# cmdc0de-apa104.net
KiCad netlist of a schematic drawn in EAGLE
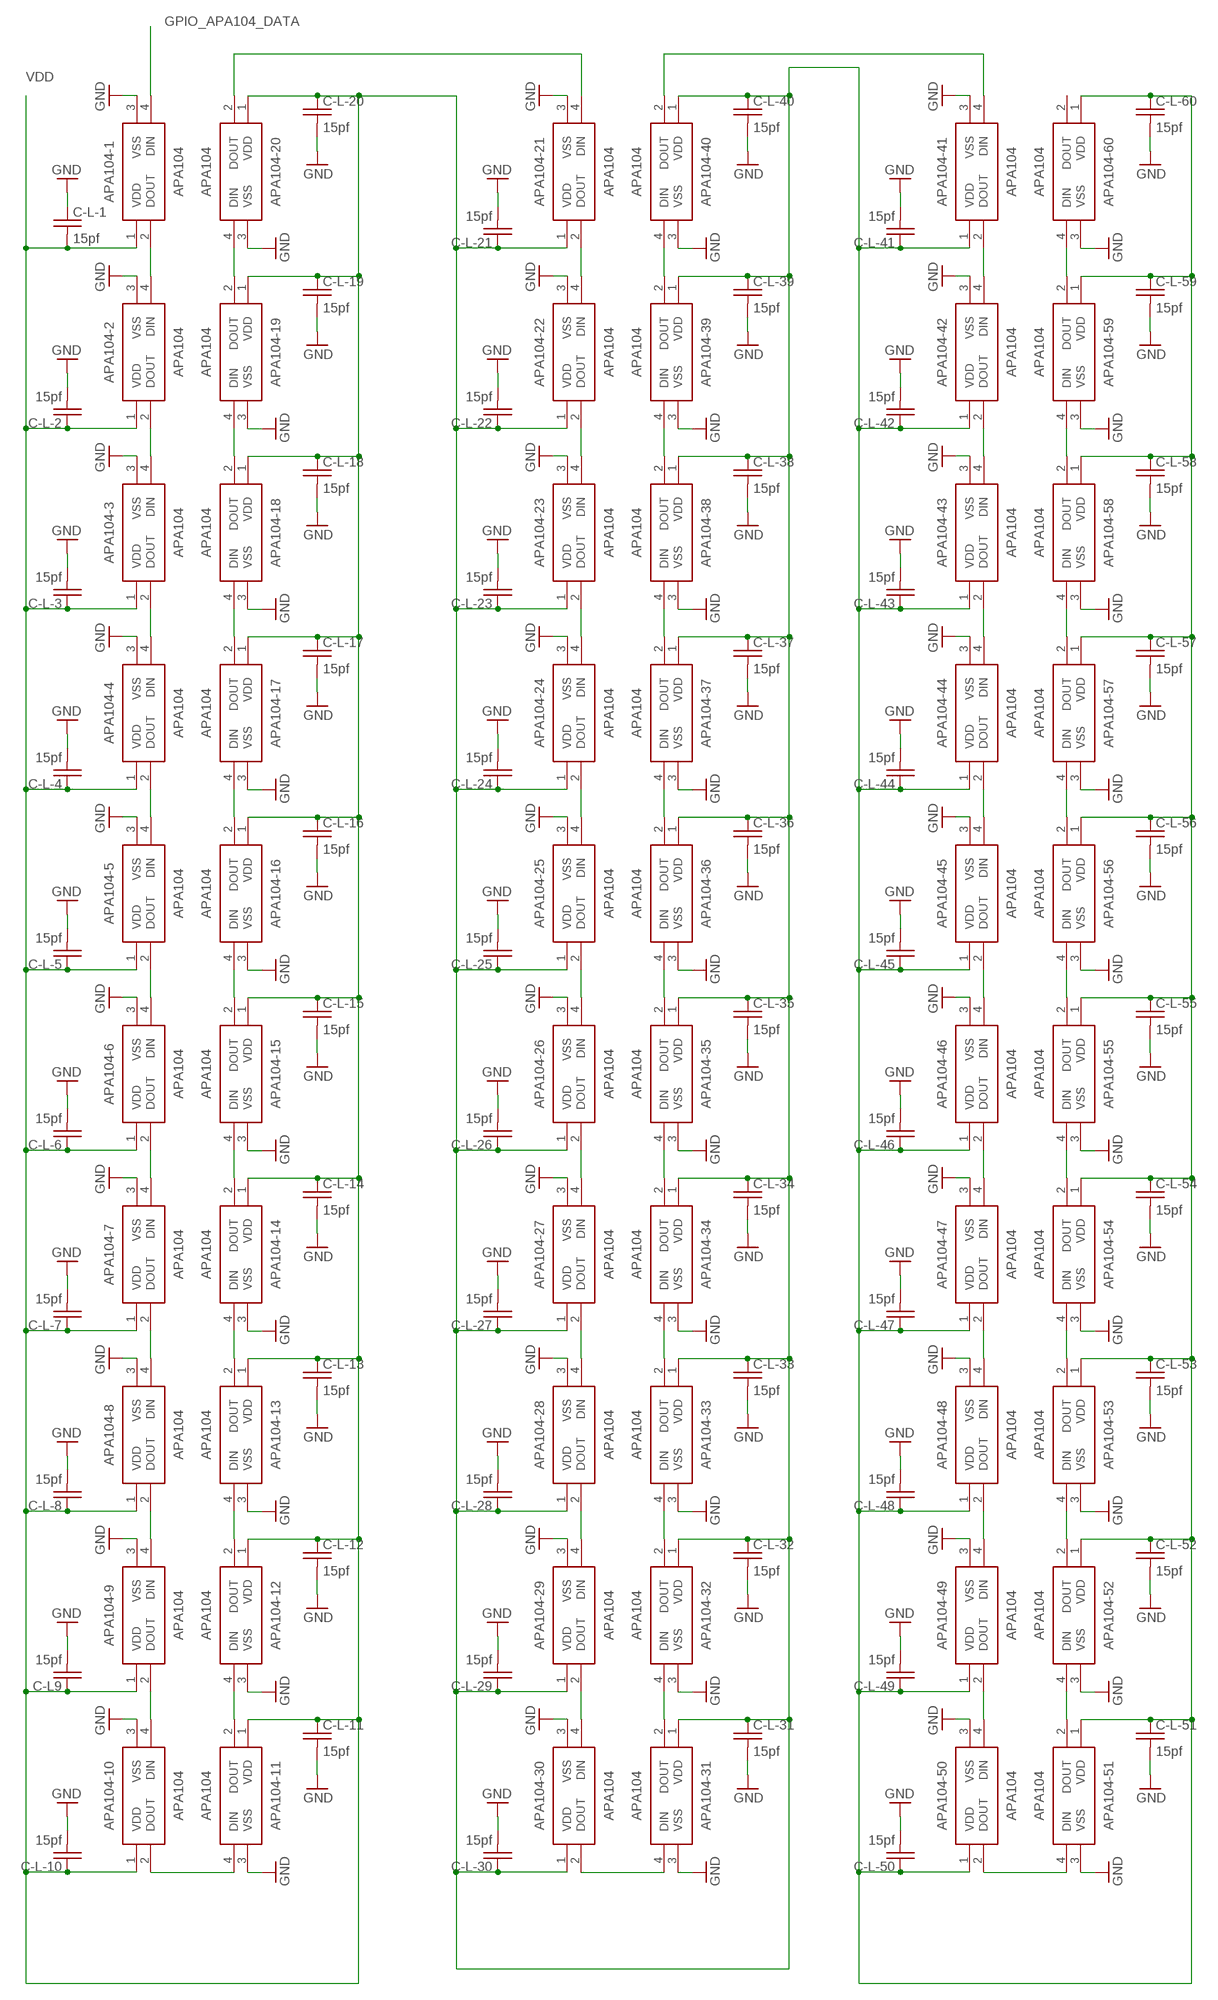
[diagram p0: schematic, sheet 1]
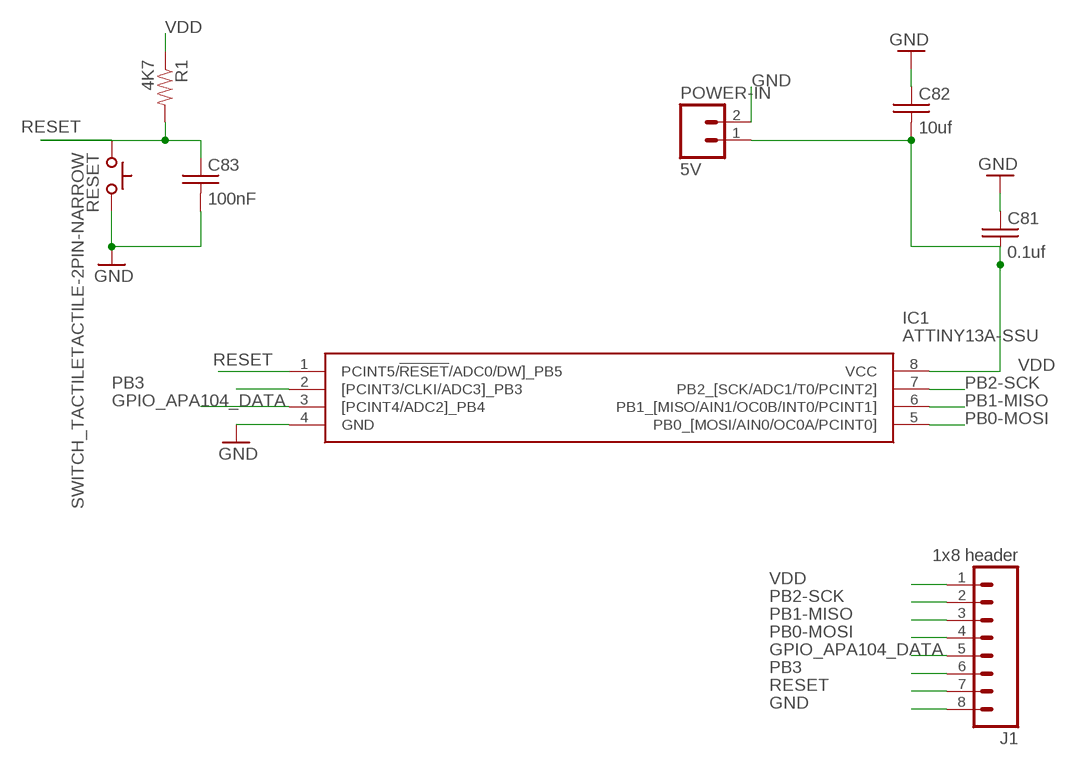
[diagram p1: schematic, sheet 2]

(export (version "E")
  (design (tool "Eeschema 10.0.6"))
  (components
    (comp (ref "C81")
      (value "0.1uf")
      (footprint "eagle-import:C0805-VOLTA")
      (libsource (lib "eagle-import") (part "C-USC0805-VOLTERA"))
    )
    (comp (ref "C82")
      (value "10uf")
      (footprint "eagle-import:C0805-VOLTA")
      (libsource (lib "eagle-import") (part "C-USC0805-VOLTERA"))
    )
    (comp (ref "C83")
      (value "100nF")
      (footprint "eagle-import:C0805-VOLTA")
      (libsource (lib "eagle-import") (part "C-USC0805-VOLTERA"))
    )
    (comp (ref "IC1")
      (value "ATTINY13A-SSU")
      (footprint "eagle-import:SOIC127P600X175-8N")
      (fields (field (name "RS_PART_NUMBER") "9214573"))
      (libsource (lib "eagle-import") (part "ATTINY13A-SSU"))
    )
    (comp (ref "J1")
      (value "1x8 header")
      (footprint "eagle-import:1X08")
      (libsource (lib "eagle-import") (part "M08SILK_FEMALE_PTH"))
    )
    (comp (ref "POWER-IN")
      (value "5V")
      (footprint "eagle-import:1X02")
      (libsource (lib "eagle-import") (part "M02PTH"))
    )
    (comp (ref "R1")
      (value "4K7")
      (footprint "eagle-import:0805")
      (libsource (lib "eagle-import") (part "RESISTOR0805-RES"))
    )
    (comp (ref "RESET")
      (value "SWITCH_TACTILETACTILE-2PIN-NARROW")
      (footprint "eagle-import:TACTILE-2PIN-NARROW")
      (libsource (lib "eagle-import") (part "SWITCH_TACTILETACTILE-2PIN-NARROW"))
    )
    (comp (ref "APA104-1")
      (value "APA104")
      (footprint "eagle-import:APA104")
      (libsource (lib "eagle-import") (part "APA104"))
    )
    (comp (ref "APA104-2")
      (value "APA104")
      (footprint "eagle-import:APA104")
      (libsource (lib "eagle-import") (part "APA104"))
    )
    (comp (ref "APA104-3")
      (value "APA104")
      (footprint "eagle-import:APA104")
      (libsource (lib "eagle-import") (part "APA104"))
    )
    (comp (ref "APA104-4")
      (value "APA104")
      (footprint "eagle-import:APA104")
      (libsource (lib "eagle-import") (part "APA104"))
    )
    (comp (ref "APA104-5")
      (value "APA104")
      (footprint "eagle-import:APA104")
      (libsource (lib "eagle-import") (part "APA104"))
    )
    (comp (ref "APA104-6")
      (value "APA104")
      (footprint "eagle-import:APA104")
      (libsource (lib "eagle-import") (part "APA104"))
    )
    (comp (ref "APA104-7")
      (value "APA104")
      (footprint "eagle-import:APA104")
      (libsource (lib "eagle-import") (part "APA104"))
    )
    (comp (ref "APA104-8")
      (value "APA104")
      (footprint "eagle-import:APA104")
      (libsource (lib "eagle-import") (part "APA104"))
    )
    (comp (ref "APA104-9")
      (value "APA104")
      (footprint "eagle-import:APA104")
      (libsource (lib "eagle-import") (part "APA104"))
    )
    (comp (ref "APA104-10")
      (value "APA104")
      (footprint "eagle-import:APA104")
      (libsource (lib "eagle-import") (part "APA104"))
    )
    (comp (ref "APA104-11")
      (value "APA104")
      (footprint "eagle-import:APA104")
      (libsource (lib "eagle-import") (part "APA104"))
    )
    (comp (ref "APA104-12")
      (value "APA104")
      (footprint "eagle-import:APA104")
      (libsource (lib "eagle-import") (part "APA104"))
    )
    (comp (ref "APA104-13")
      (value "APA104")
      (footprint "eagle-import:APA104")
      (libsource (lib "eagle-import") (part "APA104"))
    )
    (comp (ref "APA104-14")
      (value "APA104")
      (footprint "eagle-import:APA104")
      (libsource (lib "eagle-import") (part "APA104"))
    )
    (comp (ref "APA104-15")
      (value "APA104")
      (footprint "eagle-import:APA104")
      (libsource (lib "eagle-import") (part "APA104"))
    )
    (comp (ref "APA104-16")
      (value "APA104")
      (footprint "eagle-import:APA104")
      (libsource (lib "eagle-import") (part "APA104"))
    )
    (comp (ref "APA104-17")
      (value "APA104")
      (footprint "eagle-import:APA104")
      (libsource (lib "eagle-import") (part "APA104"))
    )
    (comp (ref "APA104-18")
      (value "APA104")
      (footprint "eagle-import:APA104")
      (libsource (lib "eagle-import") (part "APA104"))
    )
    (comp (ref "APA104-19")
      (value "APA104")
      (footprint "eagle-import:APA104")
      (libsource (lib "eagle-import") (part "APA104"))
    )
    (comp (ref "APA104-20")
      (value "APA104")
      (footprint "eagle-import:APA104")
      (libsource (lib "eagle-import") (part "APA104"))
    )
    (comp (ref "APA104-21")
      (value "APA104")
      (footprint "eagle-import:APA104")
      (libsource (lib "eagle-import") (part "APA104"))
    )
    (comp (ref "APA104-22")
      (value "APA104")
      (footprint "eagle-import:APA104")
      (libsource (lib "eagle-import") (part "APA104"))
    )
    (comp (ref "APA104-23")
      (value "APA104")
      (footprint "eagle-import:APA104")
      (libsource (lib "eagle-import") (part "APA104"))
    )
    (comp (ref "APA104-24")
      (value "APA104")
      (footprint "eagle-import:APA104")
      (libsource (lib "eagle-import") (part "APA104"))
    )
    (comp (ref "APA104-25")
      (value "APA104")
      (footprint "eagle-import:APA104")
      (libsource (lib "eagle-import") (part "APA104"))
    )
    (comp (ref "APA104-26")
      (value "APA104")
      (footprint "eagle-import:APA104")
      (libsource (lib "eagle-import") (part "APA104"))
    )
    (comp (ref "APA104-27")
      (value "APA104")
      (footprint "eagle-import:APA104")
      (libsource (lib "eagle-import") (part "APA104"))
    )
    (comp (ref "APA104-28")
      (value "APA104")
      (footprint "eagle-import:APA104")
      (libsource (lib "eagle-import") (part "APA104"))
    )
    (comp (ref "APA104-29")
      (value "APA104")
      (footprint "eagle-import:APA104")
      (libsource (lib "eagle-import") (part "APA104"))
    )
    (comp (ref "APA104-30")
      (value "APA104")
      (footprint "eagle-import:APA104")
      (libsource (lib "eagle-import") (part "APA104"))
    )
    (comp (ref "APA104-31")
      (value "APA104")
      (footprint "eagle-import:APA104")
      (libsource (lib "eagle-import") (part "APA104"))
    )
    (comp (ref "APA104-32")
      (value "APA104")
      (footprint "eagle-import:APA104")
      (libsource (lib "eagle-import") (part "APA104"))
    )
    (comp (ref "APA104-33")
      (value "APA104")
      (footprint "eagle-import:APA104")
      (libsource (lib "eagle-import") (part "APA104"))
    )
    (comp (ref "APA104-34")
      (value "APA104")
      (footprint "eagle-import:APA104")
      (libsource (lib "eagle-import") (part "APA104"))
    )
    (comp (ref "APA104-35")
      (value "APA104")
      (footprint "eagle-import:APA104")
      (libsource (lib "eagle-import") (part "APA104"))
    )
    (comp (ref "APA104-36")
      (value "APA104")
      (footprint "eagle-import:APA104")
      (libsource (lib "eagle-import") (part "APA104"))
    )
    (comp (ref "APA104-37")
      (value "APA104")
      (footprint "eagle-import:APA104")
      (libsource (lib "eagle-import") (part "APA104"))
    )
    (comp (ref "APA104-38")
      (value "APA104")
      (footprint "eagle-import:APA104")
      (libsource (lib "eagle-import") (part "APA104"))
    )
    (comp (ref "APA104-39")
      (value "APA104")
      (footprint "eagle-import:APA104")
      (libsource (lib "eagle-import") (part "APA104"))
    )
    (comp (ref "APA104-40")
      (value "APA104")
      (footprint "eagle-import:APA104")
      (libsource (lib "eagle-import") (part "APA104"))
    )
    (comp (ref "APA104-41")
      (value "APA104")
      (footprint "eagle-import:APA104")
      (libsource (lib "eagle-import") (part "APA104"))
    )
    (comp (ref "APA104-42")
      (value "APA104")
      (footprint "eagle-import:APA104")
      (libsource (lib "eagle-import") (part "APA104"))
    )
    (comp (ref "APA104-43")
      (value "APA104")
      (footprint "eagle-import:APA104")
      (libsource (lib "eagle-import") (part "APA104"))
    )
    (comp (ref "APA104-44")
      (value "APA104")
      (footprint "eagle-import:APA104")
      (libsource (lib "eagle-import") (part "APA104"))
    )
    (comp (ref "APA104-45")
      (value "APA104")
      (footprint "eagle-import:APA104")
      (libsource (lib "eagle-import") (part "APA104"))
    )
    (comp (ref "APA104-46")
      (value "APA104")
      (footprint "eagle-import:APA104")
      (libsource (lib "eagle-import") (part "APA104"))
    )
    (comp (ref "APA104-47")
      (value "APA104")
      (footprint "eagle-import:APA104")
      (libsource (lib "eagle-import") (part "APA104"))
    )
    (comp (ref "APA104-48")
      (value "APA104")
      (footprint "eagle-import:APA104")
      (libsource (lib "eagle-import") (part "APA104"))
    )
    (comp (ref "APA104-49")
      (value "APA104")
      (footprint "eagle-import:APA104")
      (libsource (lib "eagle-import") (part "APA104"))
    )
    (comp (ref "APA104-50")
      (value "APA104")
      (footprint "eagle-import:APA104")
      (libsource (lib "eagle-import") (part "APA104"))
    )
    (comp (ref "APA104-51")
      (value "APA104")
      (footprint "eagle-import:APA104")
      (libsource (lib "eagle-import") (part "APA104"))
    )
    (comp (ref "APA104-52")
      (value "APA104")
      (footprint "eagle-import:APA104")
      (libsource (lib "eagle-import") (part "APA104"))
    )
    (comp (ref "APA104-53")
      (value "APA104")
      (footprint "eagle-import:APA104")
      (libsource (lib "eagle-import") (part "APA104"))
    )
    (comp (ref "APA104-54")
      (value "APA104")
      (footprint "eagle-import:APA104")
      (libsource (lib "eagle-import") (part "APA104"))
    )
    (comp (ref "APA104-55")
      (value "APA104")
      (footprint "eagle-import:APA104")
      (libsource (lib "eagle-import") (part "APA104"))
    )
    (comp (ref "APA104-56")
      (value "APA104")
      (footprint "eagle-import:APA104")
      (libsource (lib "eagle-import") (part "APA104"))
    )
    (comp (ref "APA104-57")
      (value "APA104")
      (footprint "eagle-import:APA104")
      (libsource (lib "eagle-import") (part "APA104"))
    )
    (comp (ref "APA104-58")
      (value "APA104")
      (footprint "eagle-import:APA104")
      (libsource (lib "eagle-import") (part "APA104"))
    )
    (comp (ref "APA104-59")
      (value "APA104")
      (footprint "eagle-import:APA104")
      (libsource (lib "eagle-import") (part "APA104"))
    )
    (comp (ref "APA104-60")
      (value "APA104")
      (footprint "eagle-import:APA104")
      (libsource (lib "eagle-import") (part "APA104"))
    )
    (comp (ref "C-L-1")
      (value "15pf")
      (footprint "eagle-import:C0805-VOLTA")
      (libsource (lib "eagle-import") (part "C-USC0805-VOLTERA"))
    )
    (comp (ref "C-L-2")
      (value "15pf")
      (footprint "eagle-import:C0805-VOLTA")
      (libsource (lib "eagle-import") (part "C-USC0805-VOLTERA"))
    )
    (comp (ref "C-L-3")
      (value "15pf")
      (footprint "eagle-import:C0805-VOLTA")
      (libsource (lib "eagle-import") (part "C-USC0805-VOLTERA"))
    )
    (comp (ref "C-L-4")
      (value "15pf")
      (footprint "eagle-import:C0805-VOLTA")
      (libsource (lib "eagle-import") (part "C-USC0805-VOLTERA"))
    )
    (comp (ref "C-L-5")
      (value "15pf")
      (footprint "eagle-import:C0805-VOLTA")
      (libsource (lib "eagle-import") (part "C-USC0805-VOLTERA"))
    )
    (comp (ref "C-L-6")
      (value "15pf")
      (footprint "eagle-import:C0805-VOLTA")
      (libsource (lib "eagle-import") (part "C-USC0805-VOLTERA"))
    )
    (comp (ref "C-L-7")
      (value "15pf")
      (footprint "eagle-import:C0805-VOLTA")
      (libsource (lib "eagle-import") (part "C-USC0805-VOLTERA"))
    )
    (comp (ref "C-L-8")
      (value "15pf")
      (footprint "eagle-import:C0805-VOLTA")
      (libsource (lib "eagle-import") (part "C-USC0805-VOLTERA"))
    )
    (comp (ref "C-L-10")
      (value "15pf")
      (footprint "eagle-import:C0805-VOLTA")
      (libsource (lib "eagle-import") (part "C-USC0805-VOLTERA"))
    )
    (comp (ref "C-L-11")
      (value "15pf")
      (footprint "eagle-import:C0805-VOLTA")
      (libsource (lib "eagle-import") (part "C-USC0805-VOLTERA"))
    )
    (comp (ref "C-L-12")
      (value "15pf")
      (footprint "eagle-import:C0805-VOLTA")
      (libsource (lib "eagle-import") (part "C-USC0805-VOLTERA"))
    )
    (comp (ref "C-L-13")
      (value "15pf")
      (footprint "eagle-import:C0805-VOLTA")
      (libsource (lib "eagle-import") (part "C-USC0805-VOLTERA"))
    )
    (comp (ref "C-L-14")
      (value "15pf")
      (footprint "eagle-import:C0805-VOLTA")
      (libsource (lib "eagle-import") (part "C-USC0805-VOLTERA"))
    )
    (comp (ref "C-L-15")
      (value "15pf")
      (footprint "eagle-import:C0805-VOLTA")
      (libsource (lib "eagle-import") (part "C-USC0805-VOLTERA"))
    )
    (comp (ref "C-L-16")
      (value "15pf")
      (footprint "eagle-import:C0805-VOLTA")
      (libsource (lib "eagle-import") (part "C-USC0805-VOLTERA"))
    )
    (comp (ref "C-L-17")
      (value "15pf")
      (footprint "eagle-import:C0805-VOLTA")
      (libsource (lib "eagle-import") (part "C-USC0805-VOLTERA"))
    )
    (comp (ref "C-L-18")
      (value "15pf")
      (footprint "eagle-import:C0805-VOLTA")
      (libsource (lib "eagle-import") (part "C-USC0805-VOLTERA"))
    )
    (comp (ref "C-L-19")
      (value "15pf")
      (footprint "eagle-import:C0805-VOLTA")
      (libsource (lib "eagle-import") (part "C-USC0805-VOLTERA"))
    )
    (comp (ref "C-L-20")
      (value "15pf")
      (footprint "eagle-import:C0805-VOLTA")
      (libsource (lib "eagle-import") (part "C-USC0805-VOLTERA"))
    )
    (comp (ref "C-L-21")
      (value "15pf")
      (footprint "eagle-import:C0805-VOLTA")
      (libsource (lib "eagle-import") (part "C-USC0805-VOLTERA"))
    )
    (comp (ref "C-L-22")
      (value "15pf")
      (footprint "eagle-import:C0805-VOLTA")
      (libsource (lib "eagle-import") (part "C-USC0805-VOLTERA"))
    )
    (comp (ref "C-L-23")
      (value "15pf")
      (footprint "eagle-import:C0805-VOLTA")
      (libsource (lib "eagle-import") (part "C-USC0805-VOLTERA"))
    )
    (comp (ref "C-L-24")
      (value "15pf")
      (footprint "eagle-import:C0805-VOLTA")
      (libsource (lib "eagle-import") (part "C-USC0805-VOLTERA"))
    )
    (comp (ref "C-L-25")
      (value "15pf")
      (footprint "eagle-import:C0805-VOLTA")
      (libsource (lib "eagle-import") (part "C-USC0805-VOLTERA"))
    )
    (comp (ref "C-L-26")
      (value "15pf")
      (footprint "eagle-import:C0805-VOLTA")
      (libsource (lib "eagle-import") (part "C-USC0805-VOLTERA"))
    )
    (comp (ref "C-L-27")
      (value "15pf")
      (footprint "eagle-import:C0805-VOLTA")
      (libsource (lib "eagle-import") (part "C-USC0805-VOLTERA"))
    )
    (comp (ref "C-L-28")
      (value "15pf")
      (footprint "eagle-import:C0805-VOLTA")
      (libsource (lib "eagle-import") (part "C-USC0805-VOLTERA"))
    )
    (comp (ref "C-L-29")
      (value "15pf")
      (footprint "eagle-import:C0805-VOLTA")
      (libsource (lib "eagle-import") (part "C-USC0805-VOLTERA"))
    )
    (comp (ref "C-L-30")
      (value "15pf")
      (footprint "eagle-import:C0805-VOLTA")
      (libsource (lib "eagle-import") (part "C-USC0805-VOLTERA"))
    )
    (comp (ref "C-L-31")
      (value "15pf")
      (footprint "eagle-import:C0805-VOLTA")
      (libsource (lib "eagle-import") (part "C-USC0805-VOLTERA"))
    )
    (comp (ref "C-L-32")
      (value "15pf")
      (footprint "eagle-import:C0805-VOLTA")
      (libsource (lib "eagle-import") (part "C-USC0805-VOLTERA"))
    )
    (comp (ref "C-L-33")
      (value "15pf")
      (footprint "eagle-import:C0805-VOLTA")
      (libsource (lib "eagle-import") (part "C-USC0805-VOLTERA"))
    )
    (comp (ref "C-L-34")
      (value "15pf")
      (footprint "eagle-import:C0805-VOLTA")
      (libsource (lib "eagle-import") (part "C-USC0805-VOLTERA"))
    )
    (comp (ref "C-L-35")
      (value "15pf")
      (footprint "eagle-import:C0805-VOLTA")
      (libsource (lib "eagle-import") (part "C-USC0805-VOLTERA"))
    )
    (comp (ref "C-L-36")
      (value "15pf")
      (footprint "eagle-import:C0805-VOLTA")
      (libsource (lib "eagle-import") (part "C-USC0805-VOLTERA"))
    )
    (comp (ref "C-L-37")
      (value "15pf")
      (footprint "eagle-import:C0805-VOLTA")
      (libsource (lib "eagle-import") (part "C-USC0805-VOLTERA"))
    )
    (comp (ref "C-L-38")
      (value "15pf")
      (footprint "eagle-import:C0805-VOLTA")
      (libsource (lib "eagle-import") (part "C-USC0805-VOLTERA"))
    )
    (comp (ref "C-L-39")
      (value "15pf")
      (footprint "eagle-import:C0805-VOLTA")
      (libsource (lib "eagle-import") (part "C-USC0805-VOLTERA"))
    )
    (comp (ref "C-L-40")
      (value "15pf")
      (footprint "eagle-import:C0805-VOLTA")
      (libsource (lib "eagle-import") (part "C-USC0805-VOLTERA"))
    )
    (comp (ref "C-L-41")
      (value "15pf")
      (footprint "eagle-import:C0805-VOLTA")
      (libsource (lib "eagle-import") (part "C-USC0805-VOLTERA"))
    )
    (comp (ref "C-L-42")
      (value "15pf")
      (footprint "eagle-import:C0805-VOLTA")
      (libsource (lib "eagle-import") (part "C-USC0805-VOLTERA"))
    )
    (comp (ref "C-L-43")
      (value "15pf")
      (footprint "eagle-import:C0805-VOLTA")
      (libsource (lib "eagle-import") (part "C-USC0805-VOLTERA"))
    )
    (comp (ref "C-L-44")
      (value "15pf")
      (footprint "eagle-import:C0805-VOLTA")
      (libsource (lib "eagle-import") (part "C-USC0805-VOLTERA"))
    )
    (comp (ref "C-L-45")
      (value "15pf")
      (footprint "eagle-import:C0805-VOLTA")
      (libsource (lib "eagle-import") (part "C-USC0805-VOLTERA"))
    )
    (comp (ref "C-L-46")
      (value "15pf")
      (footprint "eagle-import:C0805-VOLTA")
      (libsource (lib "eagle-import") (part "C-USC0805-VOLTERA"))
    )
    (comp (ref "C-L-47")
      (value "15pf")
      (footprint "eagle-import:C0805-VOLTA")
      (libsource (lib "eagle-import") (part "C-USC0805-VOLTERA"))
    )
    (comp (ref "C-L-48")
      (value "15pf")
      (footprint "eagle-import:C0805-VOLTA")
      (libsource (lib "eagle-import") (part "C-USC0805-VOLTERA"))
    )
    (comp (ref "C-L-49")
      (value "15pf")
      (footprint "eagle-import:C0805-VOLTA")
      (libsource (lib "eagle-import") (part "C-USC0805-VOLTERA"))
    )
    (comp (ref "C-L-50")
      (value "15pf")
      (footprint "eagle-import:C0805-VOLTA")
      (libsource (lib "eagle-import") (part "C-USC0805-VOLTERA"))
    )
    (comp (ref "C-L-51")
      (value "15pf")
      (footprint "eagle-import:C0805-VOLTA")
      (libsource (lib "eagle-import") (part "C-USC0805-VOLTERA"))
    )
    (comp (ref "C-L-52")
      (value "15pf")
      (footprint "eagle-import:C0805-VOLTA")
      (libsource (lib "eagle-import") (part "C-USC0805-VOLTERA"))
    )
    (comp (ref "C-L-53")
      (value "15pf")
      (footprint "eagle-import:C0805-VOLTA")
      (libsource (lib "eagle-import") (part "C-USC0805-VOLTERA"))
    )
    (comp (ref "C-L-54")
      (value "15pf")
      (footprint "eagle-import:C0805-VOLTA")
      (libsource (lib "eagle-import") (part "C-USC0805-VOLTERA"))
    )
    (comp (ref "C-L-55")
      (value "15pf")
      (footprint "eagle-import:C0805-VOLTA")
      (libsource (lib "eagle-import") (part "C-USC0805-VOLTERA"))
    )
    (comp (ref "C-L-56")
      (value "15pf")
      (footprint "eagle-import:C0805-VOLTA")
      (libsource (lib "eagle-import") (part "C-USC0805-VOLTERA"))
    )
    (comp (ref "C-L-57")
      (value "15pf")
      (footprint "eagle-import:C0805-VOLTA")
      (libsource (lib "eagle-import") (part "C-USC0805-VOLTERA"))
    )
    (comp (ref "C-L-58")
      (value "15pf")
      (footprint "eagle-import:C0805-VOLTA")
      (libsource (lib "eagle-import") (part "C-USC0805-VOLTERA"))
    )
    (comp (ref "C-L-59")
      (value "15pf")
      (footprint "eagle-import:C0805-VOLTA")
      (libsource (lib "eagle-import") (part "C-USC0805-VOLTERA"))
    )
    (comp (ref "C-L-60")
      (value "15pf")
      (footprint "eagle-import:C0805-VOLTA")
      (libsource (lib "eagle-import") (part "C-USC0805-VOLTERA"))
    )
    (comp (ref "C-L9")
      (value "15pf")
      (footprint "eagle-import:C0805-VOLTA")
      (libsource (lib "eagle-import") (part "C-USC0805-VOLTERA"))
    )
  )
  (nets
    (net (code "1") (name "GND") (class "Default")
      (node (ref "APA104-1") (pin "3") (pinfunction "VSS_3") (pintype "power_in"))
      (node (ref "APA104-10") (pin "3") (pinfunction "VSS_3") (pintype "power_in"))
      (node (ref "APA104-11") (pin "3") (pinfunction "VSS_3") (pintype "power_in"))
      (node (ref "APA104-12") (pin "3") (pinfunction "VSS_3") (pintype "power_in"))
      (node (ref "APA104-13") (pin "3") (pinfunction "VSS_3") (pintype "power_in"))
      (node (ref "APA104-14") (pin "3") (pinfunction "VSS_3") (pintype "power_in"))
      (node (ref "APA104-15") (pin "3") (pinfunction "VSS_3") (pintype "power_in"))
      (node (ref "APA104-16") (pin "3") (pinfunction "VSS_3") (pintype "power_in"))
      (node (ref "APA104-17") (pin "3") (pinfunction "VSS_3") (pintype "power_in"))
      (node (ref "APA104-18") (pin "3") (pinfunction "VSS_3") (pintype "power_in"))
      (node (ref "APA104-19") (pin "3") (pinfunction "VSS_3") (pintype "power_in"))
      (node (ref "APA104-2") (pin "3") (pinfunction "VSS_3") (pintype "power_in"))
      (node (ref "APA104-20") (pin "3") (pinfunction "VSS_3") (pintype "power_in"))
      (node (ref "APA104-21") (pin "3") (pinfunction "VSS_3") (pintype "power_in"))
      (node (ref "APA104-22") (pin "3") (pinfunction "VSS_3") (pintype "power_in"))
      (node (ref "APA104-23") (pin "3") (pinfunction "VSS_3") (pintype "power_in"))
      (node (ref "APA104-24") (pin "3") (pinfunction "VSS_3") (pintype "power_in"))
      (node (ref "APA104-25") (pin "3") (pinfunction "VSS_3") (pintype "power_in"))
      (node (ref "APA104-26") (pin "3") (pinfunction "VSS_3") (pintype "power_in"))
      (node (ref "APA104-27") (pin "3") (pinfunction "VSS_3") (pintype "power_in"))
      (node (ref "APA104-28") (pin "3") (pinfunction "VSS_3") (pintype "power_in"))
      (node (ref "APA104-29") (pin "3") (pinfunction "VSS_3") (pintype "power_in"))
      (node (ref "APA104-3") (pin "3") (pinfunction "VSS_3") (pintype "power_in"))
      (node (ref "APA104-30") (pin "3") (pinfunction "VSS_3") (pintype "power_in"))
      (node (ref "APA104-31") (pin "3") (pinfunction "VSS_3") (pintype "power_in"))
      (node (ref "APA104-32") (pin "3") (pinfunction "VSS_3") (pintype "power_in"))
      (node (ref "APA104-33") (pin "3") (pinfunction "VSS_3") (pintype "power_in"))
      (node (ref "APA104-34") (pin "3") (pinfunction "VSS_3") (pintype "power_in"))
      (node (ref "APA104-35") (pin "3") (pinfunction "VSS_3") (pintype "power_in"))
      (node (ref "APA104-36") (pin "3") (pinfunction "VSS_3") (pintype "power_in"))
      (node (ref "APA104-37") (pin "3") (pinfunction "VSS_3") (pintype "power_in"))
      (node (ref "APA104-38") (pin "3") (pinfunction "VSS_3") (pintype "power_in"))
      (node (ref "APA104-39") (pin "3") (pinfunction "VSS_3") (pintype "power_in"))
      (node (ref "APA104-4") (pin "3") (pinfunction "VSS_3") (pintype "power_in"))
      (node (ref "APA104-40") (pin "3") (pinfunction "VSS_3") (pintype "power_in"))
      (node (ref "APA104-41") (pin "3") (pinfunction "VSS_3") (pintype "power_in"))
      (node (ref "APA104-42") (pin "3") (pinfunction "VSS_3") (pintype "power_in"))
      (node (ref "APA104-43") (pin "3") (pinfunction "VSS_3") (pintype "power_in"))
      (node (ref "APA104-44") (pin "3") (pinfunction "VSS_3") (pintype "power_in"))
      (node (ref "APA104-45") (pin "3") (pinfunction "VSS_3") (pintype "power_in"))
      (node (ref "APA104-46") (pin "3") (pinfunction "VSS_3") (pintype "power_in"))
      (node (ref "APA104-47") (pin "3") (pinfunction "VSS_3") (pintype "power_in"))
      (node (ref "APA104-48") (pin "3") (pinfunction "VSS_3") (pintype "power_in"))
      (node (ref "APA104-49") (pin "3") (pinfunction "VSS_3") (pintype "power_in"))
      (node (ref "APA104-5") (pin "3") (pinfunction "VSS_3") (pintype "power_in"))
      (node (ref "APA104-50") (pin "3") (pinfunction "VSS_3") (pintype "power_in"))
      (node (ref "APA104-51") (pin "3") (pinfunction "VSS_3") (pintype "power_in"))
      (node (ref "APA104-52") (pin "3") (pinfunction "VSS_3") (pintype "power_in"))
      (node (ref "APA104-53") (pin "3") (pinfunction "VSS_3") (pintype "power_in"))
      (node (ref "APA104-54") (pin "3") (pinfunction "VSS_3") (pintype "power_in"))
      (node (ref "APA104-55") (pin "3") (pinfunction "VSS_3") (pintype "power_in"))
      (node (ref "APA104-56") (pin "3") (pinfunction "VSS_3") (pintype "power_in"))
      (node (ref "APA104-57") (pin "3") (pinfunction "VSS_3") (pintype "power_in"))
      (node (ref "APA104-58") (pin "3") (pinfunction "VSS_3") (pintype "power_in"))
      (node (ref "APA104-59") (pin "3") (pinfunction "VSS_3") (pintype "power_in"))
      (node (ref "APA104-6") (pin "3") (pinfunction "VSS_3") (pintype "power_in"))
      (node (ref "APA104-60") (pin "3") (pinfunction "VSS_3") (pintype "power_in"))
      (node (ref "APA104-7") (pin "3") (pinfunction "VSS_3") (pintype "power_in"))
      (node (ref "APA104-8") (pin "3") (pinfunction "VSS_3") (pintype "power_in"))
      (node (ref "APA104-9") (pin "3") (pinfunction "VSS_3") (pintype "power_in"))
      (node (ref "C-L-1") (pin "1") (pinfunction "1_1") (pintype "passive"))
      (node (ref "C-L-10") (pin "2") (pinfunction "2_2") (pintype "passive"))
      (node (ref "C-L-11") (pin "2") (pinfunction "2_2") (pintype "passive"))
      (node (ref "C-L-12") (pin "2") (pinfunction "2_2") (pintype "passive"))
      (node (ref "C-L-13") (pin "2") (pinfunction "2_2") (pintype "passive"))
      (node (ref "C-L-14") (pin "2") (pinfunction "2_2") (pintype "passive"))
      (node (ref "C-L-15") (pin "2") (pinfunction "2_2") (pintype "passive"))
      (node (ref "C-L-16") (pin "2") (pinfunction "2_2") (pintype "passive"))
      (node (ref "C-L-17") (pin "2") (pinfunction "2_2") (pintype "passive"))
      (node (ref "C-L-18") (pin "2") (pinfunction "2_2") (pintype "passive"))
      (node (ref "C-L-19") (pin "2") (pinfunction "2_2") (pintype "passive"))
      (node (ref "C-L-2") (pin "2") (pinfunction "2_2") (pintype "passive"))
      (node (ref "C-L-20") (pin "2") (pinfunction "2_2") (pintype "passive"))
      (node (ref "C-L-21") (pin "2") (pinfunction "2_2") (pintype "passive"))
      (node (ref "C-L-22") (pin "2") (pinfunction "2_2") (pintype "passive"))
      (node (ref "C-L-23") (pin "2") (pinfunction "2_2") (pintype "passive"))
      (node (ref "C-L-24") (pin "2") (pinfunction "2_2") (pintype "passive"))
      (node (ref "C-L-25") (pin "2") (pinfunction "2_2") (pintype "passive"))
      (node (ref "C-L-26") (pin "2") (pinfunction "2_2") (pintype "passive"))
      (node (ref "C-L-27") (pin "2") (pinfunction "2_2") (pintype "passive"))
      (node (ref "C-L-28") (pin "2") (pinfunction "2_2") (pintype "passive"))
      (node (ref "C-L-29") (pin "2") (pinfunction "2_2") (pintype "passive"))
      (node (ref "C-L-3") (pin "2") (pinfunction "2_2") (pintype "passive"))
      (node (ref "C-L-30") (pin "2") (pinfunction "2_2") (pintype "passive"))
      (node (ref "C-L-31") (pin "2") (pinfunction "2_2") (pintype "passive"))
      (node (ref "C-L-32") (pin "2") (pinfunction "2_2") (pintype "passive"))
      (node (ref "C-L-33") (pin "2") (pinfunction "2_2") (pintype "passive"))
      (node (ref "C-L-34") (pin "2") (pinfunction "2_2") (pintype "passive"))
      (node (ref "C-L-35") (pin "2") (pinfunction "2_2") (pintype "passive"))
      (node (ref "C-L-36") (pin "2") (pinfunction "2_2") (pintype "passive"))
      (node (ref "C-L-37") (pin "2") (pinfunction "2_2") (pintype "passive"))
      (node (ref "C-L-38") (pin "2") (pinfunction "2_2") (pintype "passive"))
      (node (ref "C-L-39") (pin "2") (pinfunction "2_2") (pintype "passive"))
      (node (ref "C-L-4") (pin "2") (pinfunction "2_2") (pintype "passive"))
      (node (ref "C-L-40") (pin "2") (pinfunction "2_2") (pintype "passive"))
      (node (ref "C-L-41") (pin "2") (pinfunction "2_2") (pintype "passive"))
      (node (ref "C-L-42") (pin "2") (pinfunction "2_2") (pintype "passive"))
      (node (ref "C-L-43") (pin "2") (pinfunction "2_2") (pintype "passive"))
      (node (ref "C-L-44") (pin "2") (pinfunction "2_2") (pintype "passive"))
      (node (ref "C-L-45") (pin "2") (pinfunction "2_2") (pintype "passive"))
      (node (ref "C-L-46") (pin "2") (pinfunction "2_2") (pintype "passive"))
      (node (ref "C-L-47") (pin "2") (pinfunction "2_2") (pintype "passive"))
      (node (ref "C-L-48") (pin "2") (pinfunction "2_2") (pintype "passive"))
      (node (ref "C-L-49") (pin "2") (pinfunction "2_2") (pintype "passive"))
      (node (ref "C-L-5") (pin "2") (pinfunction "2_2") (pintype "passive"))
      (node (ref "C-L-50") (pin "2") (pinfunction "2_2") (pintype "passive"))
      (node (ref "C-L-51") (pin "2") (pinfunction "2_2") (pintype "passive"))
      (node (ref "C-L-52") (pin "2") (pinfunction "2_2") (pintype "passive"))
      (node (ref "C-L-53") (pin "2") (pinfunction "2_2") (pintype "passive"))
      (node (ref "C-L-54") (pin "2") (pinfunction "2_2") (pintype "passive"))
      (node (ref "C-L-55") (pin "2") (pinfunction "2_2") (pintype "passive"))
      (node (ref "C-L-56") (pin "2") (pinfunction "2_2") (pintype "passive"))
      (node (ref "C-L-57") (pin "2") (pinfunction "2_2") (pintype "passive"))
      (node (ref "C-L-58") (pin "2") (pinfunction "2_2") (pintype "passive"))
      (node (ref "C-L-59") (pin "2") (pinfunction "2_2") (pintype "passive"))
      (node (ref "C-L-6") (pin "2") (pinfunction "2_2") (pintype "passive"))
      (node (ref "C-L-60") (pin "2") (pinfunction "2_2") (pintype "passive"))
      (node (ref "C-L-7") (pin "2") (pinfunction "2_2") (pintype "passive"))
      (node (ref "C-L-8") (pin "2") (pinfunction "2_2") (pintype "passive"))
      (node (ref "C-L9") (pin "2") (pinfunction "2_2") (pintype "passive"))
      (node (ref "C81") (pin "1") (pinfunction "1_1") (pintype "passive"))
      (node (ref "C82") (pin "1") (pinfunction "1_1") (pintype "passive"))
      (node (ref "C83") (pin "2") (pinfunction "2_2") (pintype "passive"))
      (node (ref "IC1") (pin "4") (pinfunction "GND_4") (pintype "power_in"))
      (node (ref "J1") (pin "8") (pinfunction "8_8") (pintype "passive"))
      (node (ref "POWER-IN") (pin "2") (pinfunction "2_2") (pintype "passive"))
      (node (ref "RESET") (pin "P$1") (pinfunction "A_P$1") (pintype "passive"))
    )
    (net (code "2") (name "GPIO_APA104_DATA") (class "Default")
      (node (ref "APA104-1") (pin "4") (pinfunction "DIN_4") (pintype "input"))
      (node (ref "IC1") (pin "3") (pinfunction "[PCINT4/ADC2]_PB4_3") (pintype "input"))
      (node (ref "J1") (pin "5") (pinfunction "5_5") (pintype "passive"))
    )
    (net (code "3") (name "Net-(APA104-1-DOUT)") (class "Default")
      (node (ref "APA104-1") (pin "2") (pinfunction "DOUT_2") (pintype "output"))
      (node (ref "APA104-2") (pin "4") (pinfunction "DIN_4") (pintype "input"))
    )
    (net (code "4") (name "Net-(APA104-2-DOUT)") (class "Default")
      (node (ref "APA104-2") (pin "2") (pinfunction "DOUT_2") (pintype "output"))
      (node (ref "APA104-3") (pin "4") (pinfunction "DIN_4") (pintype "input"))
    )
    (net (code "5") (name "Net-(APA104-3-DOUT)") (class "Default")
      (node (ref "APA104-3") (pin "2") (pinfunction "DOUT_2") (pintype "output"))
      (node (ref "APA104-4") (pin "4") (pinfunction "DIN_4") (pintype "input"))
    )
    (net (code "6") (name "Net-(APA104-4-DOUT)") (class "Default")
      (node (ref "APA104-4") (pin "2") (pinfunction "DOUT_2") (pintype "output"))
      (node (ref "APA104-5") (pin "4") (pinfunction "DIN_4") (pintype "input"))
    )
    (net (code "7") (name "Net-(APA104-5-DOUT)") (class "Default")
      (node (ref "APA104-5") (pin "2") (pinfunction "DOUT_2") (pintype "output"))
      (node (ref "APA104-6") (pin "4") (pinfunction "DIN_4") (pintype "input"))
    )
    (net (code "8") (name "Net-(APA104-6-DOUT)") (class "Default")
      (node (ref "APA104-6") (pin "2") (pinfunction "DOUT_2") (pintype "output"))
      (node (ref "APA104-7") (pin "4") (pinfunction "DIN_4") (pintype "input"))
    )
    (net (code "9") (name "Net-(APA104-7-DOUT)") (class "Default")
      (node (ref "APA104-7") (pin "2") (pinfunction "DOUT_2") (pintype "output"))
      (node (ref "APA104-8") (pin "4") (pinfunction "DIN_4") (pintype "input"))
    )
    (net (code "10") (name "Net-(APA104-8-DOUT)") (class "Default")
      (node (ref "APA104-8") (pin "2") (pinfunction "DOUT_2") (pintype "output"))
      (node (ref "APA104-9") (pin "4") (pinfunction "DIN_4") (pintype "input"))
    )
    (net (code "11") (name "Net-(APA104-10-DIN)") (class "Default")
      (node (ref "APA104-10") (pin "4") (pinfunction "DIN_4") (pintype "input"))
      (node (ref "APA104-9") (pin "2") (pinfunction "DOUT_2") (pintype "output"))
    )
    (net (code "12") (name "Net-(APA104-10-DOUT)") (class "Default")
      (node (ref "APA104-10") (pin "2") (pinfunction "DOUT_2") (pintype "output"))
      (node (ref "APA104-11") (pin "4") (pinfunction "DIN_4") (pintype "input"))
    )
    (net (code "13") (name "Net-(APA104-11-DOUT)") (class "Default")
      (node (ref "APA104-11") (pin "2") (pinfunction "DOUT_2") (pintype "output"))
      (node (ref "APA104-12") (pin "4") (pinfunction "DIN_4") (pintype "input"))
    )
    (net (code "14") (name "Net-(APA104-12-DOUT)") (class "Default")
      (node (ref "APA104-12") (pin "2") (pinfunction "DOUT_2") (pintype "output"))
      (node (ref "APA104-13") (pin "4") (pinfunction "DIN_4") (pintype "input"))
    )
    (net (code "15") (name "Net-(APA104-13-DOUT)") (class "Default")
      (node (ref "APA104-13") (pin "2") (pinfunction "DOUT_2") (pintype "output"))
      (node (ref "APA104-14") (pin "4") (pinfunction "DIN_4") (pintype "input"))
    )
    (net (code "16") (name "Net-(APA104-14-DOUT)") (class "Default")
      (node (ref "APA104-14") (pin "2") (pinfunction "DOUT_2") (pintype "output"))
      (node (ref "APA104-15") (pin "4") (pinfunction "DIN_4") (pintype "input"))
    )
    (net (code "17") (name "Net-(APA104-15-DOUT)") (class "Default")
      (node (ref "APA104-15") (pin "2") (pinfunction "DOUT_2") (pintype "output"))
      (node (ref "APA104-16") (pin "4") (pinfunction "DIN_4") (pintype "input"))
    )
    (net (code "18") (name "Net-(APA104-16-DOUT)") (class "Default")
      (node (ref "APA104-16") (pin "2") (pinfunction "DOUT_2") (pintype "output"))
      (node (ref "APA104-17") (pin "4") (pinfunction "DIN_4") (pintype "input"))
    )
    (net (code "19") (name "Net-(APA104-17-DOUT)") (class "Default")
      (node (ref "APA104-17") (pin "2") (pinfunction "DOUT_2") (pintype "output"))
      (node (ref "APA104-18") (pin "4") (pinfunction "DIN_4") (pintype "input"))
    )
    (net (code "20") (name "Net-(APA104-18-DOUT)") (class "Default")
      (node (ref "APA104-18") (pin "2") (pinfunction "DOUT_2") (pintype "output"))
      (node (ref "APA104-19") (pin "4") (pinfunction "DIN_4") (pintype "input"))
    )
    (net (code "21") (name "Net-(APA104-19-DOUT)") (class "Default")
      (node (ref "APA104-19") (pin "2") (pinfunction "DOUT_2") (pintype "output"))
      (node (ref "APA104-20") (pin "4") (pinfunction "DIN_4") (pintype "input"))
    )
    (net (code "22") (name "Net-(APA104-20-DOUT)") (class "Default")
      (node (ref "APA104-20") (pin "2") (pinfunction "DOUT_2") (pintype "output"))
      (node (ref "APA104-21") (pin "4") (pinfunction "DIN_4") (pintype "input"))
    )
    (net (code "23") (name "Net-(APA104-21-DOUT)") (class "Default")
      (node (ref "APA104-21") (pin "2") (pinfunction "DOUT_2") (pintype "output"))
      (node (ref "APA104-22") (pin "4") (pinfunction "DIN_4") (pintype "input"))
    )
    (net (code "24") (name "Net-(APA104-22-DOUT)") (class "Default")
      (node (ref "APA104-22") (pin "2") (pinfunction "DOUT_2") (pintype "output"))
      (node (ref "APA104-23") (pin "4") (pinfunction "DIN_4") (pintype "input"))
    )
    (net (code "25") (name "Net-(APA104-23-DOUT)") (class "Default")
      (node (ref "APA104-23") (pin "2") (pinfunction "DOUT_2") (pintype "output"))
      (node (ref "APA104-24") (pin "4") (pinfunction "DIN_4") (pintype "input"))
    )
    (net (code "26") (name "Net-(APA104-24-DOUT)") (class "Default")
      (node (ref "APA104-24") (pin "2") (pinfunction "DOUT_2") (pintype "output"))
      (node (ref "APA104-25") (pin "4") (pinfunction "DIN_4") (pintype "input"))
    )
    (net (code "27") (name "Net-(APA104-25-DOUT)") (class "Default")
      (node (ref "APA104-25") (pin "2") (pinfunction "DOUT_2") (pintype "output"))
      (node (ref "APA104-26") (pin "4") (pinfunction "DIN_4") (pintype "input"))
    )
    (net (code "28") (name "Net-(APA104-26-DOUT)") (class "Default")
      (node (ref "APA104-26") (pin "2") (pinfunction "DOUT_2") (pintype "output"))
      (node (ref "APA104-27") (pin "4") (pinfunction "DIN_4") (pintype "input"))
    )
    (net (code "29") (name "Net-(APA104-27-DOUT)") (class "Default")
      (node (ref "APA104-27") (pin "2") (pinfunction "DOUT_2") (pintype "output"))
      (node (ref "APA104-28") (pin "4") (pinfunction "DIN_4") (pintype "input"))
    )
    (net (code "30") (name "Net-(APA104-28-DOUT)") (class "Default")
      (node (ref "APA104-28") (pin "2") (pinfunction "DOUT_2") (pintype "output"))
      (node (ref "APA104-29") (pin "4") (pinfunction "DIN_4") (pintype "input"))
    )
    (net (code "31") (name "Net-(APA104-29-DOUT)") (class "Default")
      (node (ref "APA104-29") (pin "2") (pinfunction "DOUT_2") (pintype "output"))
      (node (ref "APA104-30") (pin "4") (pinfunction "DIN_4") (pintype "input"))
    )
    (net (code "32") (name "Net-(APA104-30-DOUT)") (class "Default")
      (node (ref "APA104-30") (pin "2") (pinfunction "DOUT_2") (pintype "output"))
      (node (ref "APA104-31") (pin "4") (pinfunction "DIN_4") (pintype "input"))
    )
    (net (code "33") (name "Net-(APA104-31-DOUT)") (class "Default")
      (node (ref "APA104-31") (pin "2") (pinfunction "DOUT_2") (pintype "output"))
      (node (ref "APA104-32") (pin "4") (pinfunction "DIN_4") (pintype "input"))
    )
    (net (code "34") (name "Net-(APA104-32-DOUT)") (class "Default")
      (node (ref "APA104-32") (pin "2") (pinfunction "DOUT_2") (pintype "output"))
      (node (ref "APA104-33") (pin "4") (pinfunction "DIN_4") (pintype "input"))
    )
    (net (code "35") (name "Net-(APA104-33-DOUT)") (class "Default")
      (node (ref "APA104-33") (pin "2") (pinfunction "DOUT_2") (pintype "output"))
      (node (ref "APA104-34") (pin "4") (pinfunction "DIN_4") (pintype "input"))
    )
    (net (code "36") (name "Net-(APA104-34-DOUT)") (class "Default")
      (node (ref "APA104-34") (pin "2") (pinfunction "DOUT_2") (pintype "output"))
      (node (ref "APA104-35") (pin "4") (pinfunction "DIN_4") (pintype "input"))
    )
    (net (code "37") (name "Net-(APA104-35-DOUT)") (class "Default")
      (node (ref "APA104-35") (pin "2") (pinfunction "DOUT_2") (pintype "output"))
      (node (ref "APA104-36") (pin "4") (pinfunction "DIN_4") (pintype "input"))
    )
    (net (code "38") (name "Net-(APA104-36-DOUT)") (class "Default")
      (node (ref "APA104-36") (pin "2") (pinfunction "DOUT_2") (pintype "output"))
      (node (ref "APA104-37") (pin "4") (pinfunction "DIN_4") (pintype "input"))
    )
    (net (code "39") (name "Net-(APA104-37-DOUT)") (class "Default")
      (node (ref "APA104-37") (pin "2") (pinfunction "DOUT_2") (pintype "output"))
      (node (ref "APA104-38") (pin "4") (pinfunction "DIN_4") (pintype "input"))
    )
    (net (code "40") (name "Net-(APA104-38-DOUT)") (class "Default")
      (node (ref "APA104-38") (pin "2") (pinfunction "DOUT_2") (pintype "output"))
      (node (ref "APA104-39") (pin "4") (pinfunction "DIN_4") (pintype "input"))
    )
    (net (code "41") (name "Net-(APA104-39-DOUT)") (class "Default")
      (node (ref "APA104-39") (pin "2") (pinfunction "DOUT_2") (pintype "output"))
      (node (ref "APA104-40") (pin "4") (pinfunction "DIN_4") (pintype "input"))
    )
    (net (code "42") (name "Net-(APA104-40-DOUT)") (class "Default")
      (node (ref "APA104-40") (pin "2") (pinfunction "DOUT_2") (pintype "output"))
      (node (ref "APA104-41") (pin "4") (pinfunction "DIN_4") (pintype "input"))
    )
    (net (code "43") (name "Net-(APA104-41-DOUT)") (class "Default")
      (node (ref "APA104-41") (pin "2") (pinfunction "DOUT_2") (pintype "output"))
      (node (ref "APA104-42") (pin "4") (pinfunction "DIN_4") (pintype "input"))
    )
    (net (code "44") (name "Net-(APA104-42-DOUT)") (class "Default")
      (node (ref "APA104-42") (pin "2") (pinfunction "DOUT_2") (pintype "output"))
      (node (ref "APA104-43") (pin "4") (pinfunction "DIN_4") (pintype "input"))
    )
    (net (code "45") (name "Net-(APA104-43-DOUT)") (class "Default")
      (node (ref "APA104-43") (pin "2") (pinfunction "DOUT_2") (pintype "output"))
      (node (ref "APA104-44") (pin "4") (pinfunction "DIN_4") (pintype "input"))
    )
    (net (code "46") (name "Net-(APA104-44-DOUT)") (class "Default")
      (node (ref "APA104-44") (pin "2") (pinfunction "DOUT_2") (pintype "output"))
      (node (ref "APA104-45") (pin "4") (pinfunction "DIN_4") (pintype "input"))
    )
    (net (code "47") (name "Net-(APA104-45-DOUT)") (class "Default")
      (node (ref "APA104-45") (pin "2") (pinfunction "DOUT_2") (pintype "output"))
      (node (ref "APA104-46") (pin "4") (pinfunction "DIN_4") (pintype "input"))
    )
    (net (code "48") (name "Net-(APA104-46-DOUT)") (class "Default")
      (node (ref "APA104-46") (pin "2") (pinfunction "DOUT_2") (pintype "output"))
      (node (ref "APA104-47") (pin "4") (pinfunction "DIN_4") (pintype "input"))
    )
    (net (code "49") (name "Net-(APA104-47-DOUT)") (class "Default")
      (node (ref "APA104-47") (pin "2") (pinfunction "DOUT_2") (pintype "output"))
      (node (ref "APA104-48") (pin "4") (pinfunction "DIN_4") (pintype "input"))
    )
    (net (code "50") (name "Net-(APA104-48-DOUT)") (class "Default")
      (node (ref "APA104-48") (pin "2") (pinfunction "DOUT_2") (pintype "output"))
      (node (ref "APA104-49") (pin "4") (pinfunction "DIN_4") (pintype "input"))
    )
    (net (code "51") (name "Net-(APA104-49-DOUT)") (class "Default")
      (node (ref "APA104-49") (pin "2") (pinfunction "DOUT_2") (pintype "output"))
      (node (ref "APA104-50") (pin "4") (pinfunction "DIN_4") (pintype "input"))
    )
    (net (code "52") (name "Net-(APA104-50-DOUT)") (class "Default")
      (node (ref "APA104-50") (pin "2") (pinfunction "DOUT_2") (pintype "output"))
      (node (ref "APA104-51") (pin "4") (pinfunction "DIN_4") (pintype "input"))
    )
    (net (code "53") (name "Net-(APA104-51-DOUT)") (class "Default")
      (node (ref "APA104-51") (pin "2") (pinfunction "DOUT_2") (pintype "output"))
      (node (ref "APA104-52") (pin "4") (pinfunction "DIN_4") (pintype "input"))
    )
    (net (code "54") (name "Net-(APA104-52-DOUT)") (class "Default")
      (node (ref "APA104-52") (pin "2") (pinfunction "DOUT_2") (pintype "output"))
      (node (ref "APA104-53") (pin "4") (pinfunction "DIN_4") (pintype "input"))
    )
    (net (code "55") (name "Net-(APA104-53-DOUT)") (class "Default")
      (node (ref "APA104-53") (pin "2") (pinfunction "DOUT_2") (pintype "output"))
      (node (ref "APA104-54") (pin "4") (pinfunction "DIN_4") (pintype "input"))
    )
    (net (code "56") (name "Net-(APA104-54-DOUT)") (class "Default")
      (node (ref "APA104-54") (pin "2") (pinfunction "DOUT_2") (pintype "output"))
      (node (ref "APA104-55") (pin "4") (pinfunction "DIN_4") (pintype "input"))
    )
    (net (code "57") (name "Net-(APA104-55-DOUT)") (class "Default")
      (node (ref "APA104-55") (pin "2") (pinfunction "DOUT_2") (pintype "output"))
      (node (ref "APA104-56") (pin "4") (pinfunction "DIN_4") (pintype "input"))
    )
    (net (code "58") (name "Net-(APA104-56-DOUT)") (class "Default")
      (node (ref "APA104-56") (pin "2") (pinfunction "DOUT_2") (pintype "output"))
      (node (ref "APA104-57") (pin "4") (pinfunction "DIN_4") (pintype "input"))
    )
    (net (code "59") (name "Net-(APA104-57-DOUT)") (class "Default")
      (node (ref "APA104-57") (pin "2") (pinfunction "DOUT_2") (pintype "output"))
      (node (ref "APA104-58") (pin "4") (pinfunction "DIN_4") (pintype "input"))
    )
    (net (code "60") (name "Net-(APA104-58-DOUT)") (class "Default")
      (node (ref "APA104-58") (pin "2") (pinfunction "DOUT_2") (pintype "output"))
      (node (ref "APA104-59") (pin "4") (pinfunction "DIN_4") (pintype "input"))
    )
    (net (code "61") (name "Net-(APA104-59-DOUT)") (class "Default")
      (node (ref "APA104-59") (pin "2") (pinfunction "DOUT_2") (pintype "output"))
      (node (ref "APA104-60") (pin "4") (pinfunction "DIN_4") (pintype "input"))
    )
    (net (code "62") (name "PB0-MOSI") (class "Default")
      (node (ref "IC1") (pin "5") (pinfunction "PB0_[MOSI/AIN0/OC0A/PCINT0]_5") (pintype "input"))
      (node (ref "J1") (pin "4") (pinfunction "4_4") (pintype "passive"))
    )
    (net (code "63") (name "PB1-MISO") (class "Default")
      (node (ref "IC1") (pin "6") (pinfunction "PB1_[MISO/AIN1/OC0B/INT0/PCINT1]_6") (pintype "input"))
      (node (ref "J1") (pin "3") (pinfunction "3_3") (pintype "passive"))
    )
    (net (code "64") (name "PB2-SCK") (class "Default")
      (node (ref "IC1") (pin "7") (pinfunction "PB2_[SCK/ADC1/T0/PCINT2]_7") (pintype "input"))
      (node (ref "J1") (pin "2") (pinfunction "2_2") (pintype "passive"))
    )
    (net (code "65") (name "PB3") (class "Default")
      (node (ref "IC1") (pin "2") (pinfunction "[PCINT3/CLKI/ADC3]_PB3_2") (pintype "input"))
      (node (ref "J1") (pin "6") (pinfunction "6_6") (pintype "passive"))
    )
    (net (code "66") (name "RESET") (class "Default")
      (node (ref "C83") (pin "1") (pinfunction "1_1") (pintype "passive"))
      (node (ref "IC1") (pin "1") (pinfunction "PCINT5/~{RESET}/ADC0/DW]_PB5_1") (pintype "input"))
      (node (ref "J1") (pin "7") (pinfunction "7_7") (pintype "passive"))
      (node (ref "R1") (pin "2") (pinfunction "2_2") (pintype "passive"))
      (node (ref "RESET") (pin "P$2") (pinfunction "C_P$2") (pintype "passive"))
    )
    (net (code "67") (name "VDD") (class "Default")
      (node (ref "APA104-1") (pin "1") (pinfunction "VDD_1") (pintype "power_in"))
      (node (ref "APA104-10") (pin "1") (pinfunction "VDD_1") (pintype "power_in"))
      (node (ref "APA104-11") (pin "1") (pinfunction "VDD_1") (pintype "power_in"))
      (node (ref "APA104-12") (pin "1") (pinfunction "VDD_1") (pintype "power_in"))
      (node (ref "APA104-13") (pin "1") (pinfunction "VDD_1") (pintype "power_in"))
      (node (ref "APA104-14") (pin "1") (pinfunction "VDD_1") (pintype "power_in"))
      (node (ref "APA104-15") (pin "1") (pinfunction "VDD_1") (pintype "power_in"))
      (node (ref "APA104-16") (pin "1") (pinfunction "VDD_1") (pintype "power_in"))
      (node (ref "APA104-17") (pin "1") (pinfunction "VDD_1") (pintype "power_in"))
      (node (ref "APA104-18") (pin "1") (pinfunction "VDD_1") (pintype "power_in"))
      (node (ref "APA104-19") (pin "1") (pinfunction "VDD_1") (pintype "power_in"))
      (node (ref "APA104-2") (pin "1") (pinfunction "VDD_1") (pintype "power_in"))
      (node (ref "APA104-20") (pin "1") (pinfunction "VDD_1") (pintype "power_in"))
      (node (ref "APA104-21") (pin "1") (pinfunction "VDD_1") (pintype "power_in"))
      (node (ref "APA104-22") (pin "1") (pinfunction "VDD_1") (pintype "power_in"))
      (node (ref "APA104-23") (pin "1") (pinfunction "VDD_1") (pintype "power_in"))
      (node (ref "APA104-24") (pin "1") (pinfunction "VDD_1") (pintype "power_in"))
      (node (ref "APA104-25") (pin "1") (pinfunction "VDD_1") (pintype "power_in"))
      (node (ref "APA104-26") (pin "1") (pinfunction "VDD_1") (pintype "power_in"))
      (node (ref "APA104-27") (pin "1") (pinfunction "VDD_1") (pintype "power_in"))
      (node (ref "APA104-28") (pin "1") (pinfunction "VDD_1") (pintype "power_in"))
      (node (ref "APA104-29") (pin "1") (pinfunction "VDD_1") (pintype "power_in"))
      (node (ref "APA104-3") (pin "1") (pinfunction "VDD_1") (pintype "power_in"))
      (node (ref "APA104-30") (pin "1") (pinfunction "VDD_1") (pintype "power_in"))
      (node (ref "APA104-31") (pin "1") (pinfunction "VDD_1") (pintype "power_in"))
      (node (ref "APA104-32") (pin "1") (pinfunction "VDD_1") (pintype "power_in"))
      (node (ref "APA104-33") (pin "1") (pinfunction "VDD_1") (pintype "power_in"))
      (node (ref "APA104-34") (pin "1") (pinfunction "VDD_1") (pintype "power_in"))
      (node (ref "APA104-35") (pin "1") (pinfunction "VDD_1") (pintype "power_in"))
      (node (ref "APA104-36") (pin "1") (pinfunction "VDD_1") (pintype "power_in"))
      (node (ref "APA104-37") (pin "1") (pinfunction "VDD_1") (pintype "power_in"))
      (node (ref "APA104-38") (pin "1") (pinfunction "VDD_1") (pintype "power_in"))
      (node (ref "APA104-39") (pin "1") (pinfunction "VDD_1") (pintype "power_in"))
      (node (ref "APA104-4") (pin "1") (pinfunction "VDD_1") (pintype "power_in"))
      (node (ref "APA104-40") (pin "1") (pinfunction "VDD_1") (pintype "power_in"))
      (node (ref "APA104-41") (pin "1") (pinfunction "VDD_1") (pintype "power_in"))
      (node (ref "APA104-42") (pin "1") (pinfunction "VDD_1") (pintype "power_in"))
      (node (ref "APA104-43") (pin "1") (pinfunction "VDD_1") (pintype "power_in"))
      (node (ref "APA104-44") (pin "1") (pinfunction "VDD_1") (pintype "power_in"))
      (node (ref "APA104-45") (pin "1") (pinfunction "VDD_1") (pintype "power_in"))
      (node (ref "APA104-46") (pin "1") (pinfunction "VDD_1") (pintype "power_in"))
      (node (ref "APA104-47") (pin "1") (pinfunction "VDD_1") (pintype "power_in"))
      (node (ref "APA104-48") (pin "1") (pinfunction "VDD_1") (pintype "power_in"))
      (node (ref "APA104-49") (pin "1") (pinfunction "VDD_1") (pintype "power_in"))
      (node (ref "APA104-5") (pin "1") (pinfunction "VDD_1") (pintype "power_in"))
      (node (ref "APA104-50") (pin "1") (pinfunction "VDD_1") (pintype "power_in"))
      (node (ref "APA104-51") (pin "1") (pinfunction "VDD_1") (pintype "power_in"))
      (node (ref "APA104-52") (pin "1") (pinfunction "VDD_1") (pintype "power_in"))
      (node (ref "APA104-53") (pin "1") (pinfunction "VDD_1") (pintype "power_in"))
      (node (ref "APA104-54") (pin "1") (pinfunction "VDD_1") (pintype "power_in"))
      (node (ref "APA104-55") (pin "1") (pinfunction "VDD_1") (pintype "power_in"))
      (node (ref "APA104-56") (pin "1") (pinfunction "VDD_1") (pintype "power_in"))
      (node (ref "APA104-57") (pin "1") (pinfunction "VDD_1") (pintype "power_in"))
      (node (ref "APA104-58") (pin "1") (pinfunction "VDD_1") (pintype "power_in"))
      (node (ref "APA104-59") (pin "1") (pinfunction "VDD_1") (pintype "power_in"))
      (node (ref "APA104-6") (pin "1") (pinfunction "VDD_1") (pintype "power_in"))
      (node (ref "APA104-60") (pin "1") (pinfunction "VDD_1") (pintype "power_in"))
      (node (ref "APA104-7") (pin "1") (pinfunction "VDD_1") (pintype "power_in"))
      (node (ref "APA104-8") (pin "1") (pinfunction "VDD_1") (pintype "power_in"))
      (node (ref "APA104-9") (pin "1") (pinfunction "VDD_1") (pintype "power_in"))
      (node (ref "C-L-1") (pin "2") (pinfunction "2_2") (pintype "passive"))
      (node (ref "C-L-10") (pin "1") (pinfunction "1_1") (pintype "passive"))
      (node (ref "C-L-11") (pin "1") (pinfunction "1_1") (pintype "passive"))
      (node (ref "C-L-12") (pin "1") (pinfunction "1_1") (pintype "passive"))
      (node (ref "C-L-13") (pin "1") (pinfunction "1_1") (pintype "passive"))
      (node (ref "C-L-14") (pin "1") (pinfunction "1_1") (pintype "passive"))
      (node (ref "C-L-15") (pin "1") (pinfunction "1_1") (pintype "passive"))
      (node (ref "C-L-16") (pin "1") (pinfunction "1_1") (pintype "passive"))
      (node (ref "C-L-17") (pin "1") (pinfunction "1_1") (pintype "passive"))
      (node (ref "C-L-18") (pin "1") (pinfunction "1_1") (pintype "passive"))
      (node (ref "C-L-19") (pin "1") (pinfunction "1_1") (pintype "passive"))
      (node (ref "C-L-2") (pin "1") (pinfunction "1_1") (pintype "passive"))
      (node (ref "C-L-20") (pin "1") (pinfunction "1_1") (pintype "passive"))
      (node (ref "C-L-21") (pin "1") (pinfunction "1_1") (pintype "passive"))
      (node (ref "C-L-22") (pin "1") (pinfunction "1_1") (pintype "passive"))
      (node (ref "C-L-23") (pin "1") (pinfunction "1_1") (pintype "passive"))
      (node (ref "C-L-24") (pin "1") (pinfunction "1_1") (pintype "passive"))
      (node (ref "C-L-25") (pin "1") (pinfunction "1_1") (pintype "passive"))
      (node (ref "C-L-26") (pin "1") (pinfunction "1_1") (pintype "passive"))
      (node (ref "C-L-27") (pin "1") (pinfunction "1_1") (pintype "passive"))
      (node (ref "C-L-28") (pin "1") (pinfunction "1_1") (pintype "passive"))
      (node (ref "C-L-29") (pin "1") (pinfunction "1_1") (pintype "passive"))
      (node (ref "C-L-3") (pin "1") (pinfunction "1_1") (pintype "passive"))
      (node (ref "C-L-30") (pin "1") (pinfunction "1_1") (pintype "passive"))
      (node (ref "C-L-31") (pin "1") (pinfunction "1_1") (pintype "passive"))
      (node (ref "C-L-32") (pin "1") (pinfunction "1_1") (pintype "passive"))
      (node (ref "C-L-33") (pin "1") (pinfunction "1_1") (pintype "passive"))
      (node (ref "C-L-34") (pin "1") (pinfunction "1_1") (pintype "passive"))
      (node (ref "C-L-35") (pin "1") (pinfunction "1_1") (pintype "passive"))
      (node (ref "C-L-36") (pin "1") (pinfunction "1_1") (pintype "passive"))
      (node (ref "C-L-37") (pin "1") (pinfunction "1_1") (pintype "passive"))
      (node (ref "C-L-38") (pin "1") (pinfunction "1_1") (pintype "passive"))
      (node (ref "C-L-39") (pin "1") (pinfunction "1_1") (pintype "passive"))
      (node (ref "C-L-4") (pin "1") (pinfunction "1_1") (pintype "passive"))
      (node (ref "C-L-40") (pin "1") (pinfunction "1_1") (pintype "passive"))
      (node (ref "C-L-41") (pin "1") (pinfunction "1_1") (pintype "passive"))
      (node (ref "C-L-42") (pin "1") (pinfunction "1_1") (pintype "passive"))
      (node (ref "C-L-43") (pin "1") (pinfunction "1_1") (pintype "passive"))
      (node (ref "C-L-44") (pin "1") (pinfunction "1_1") (pintype "passive"))
      (node (ref "C-L-45") (pin "1") (pinfunction "1_1") (pintype "passive"))
      (node (ref "C-L-46") (pin "1") (pinfunction "1_1") (pintype "passive"))
      (node (ref "C-L-47") (pin "1") (pinfunction "1_1") (pintype "passive"))
      (node (ref "C-L-48") (pin "1") (pinfunction "1_1") (pintype "passive"))
      (node (ref "C-L-49") (pin "1") (pinfunction "1_1") (pintype "passive"))
      (node (ref "C-L-5") (pin "1") (pinfunction "1_1") (pintype "passive"))
      (node (ref "C-L-50") (pin "1") (pinfunction "1_1") (pintype "passive"))
      (node (ref "C-L-51") (pin "1") (pinfunction "1_1") (pintype "passive"))
      (node (ref "C-L-52") (pin "1") (pinfunction "1_1") (pintype "passive"))
      (node (ref "C-L-53") (pin "1") (pinfunction "1_1") (pintype "passive"))
      (node (ref "C-L-54") (pin "1") (pinfunction "1_1") (pintype "passive"))
      (node (ref "C-L-55") (pin "1") (pinfunction "1_1") (pintype "passive"))
      (node (ref "C-L-56") (pin "1") (pinfunction "1_1") (pintype "passive"))
      (node (ref "C-L-57") (pin "1") (pinfunction "1_1") (pintype "passive"))
      (node (ref "C-L-58") (pin "1") (pinfunction "1_1") (pintype "passive"))
      (node (ref "C-L-59") (pin "1") (pinfunction "1_1") (pintype "passive"))
      (node (ref "C-L-6") (pin "1") (pinfunction "1_1") (pintype "passive"))
      (node (ref "C-L-60") (pin "1") (pinfunction "1_1") (pintype "passive"))
      (node (ref "C-L-7") (pin "1") (pinfunction "1_1") (pintype "passive"))
      (node (ref "C-L-8") (pin "1") (pinfunction "1_1") (pintype "passive"))
      (node (ref "C-L9") (pin "1") (pinfunction "1_1") (pintype "passive"))
      (node (ref "C81") (pin "2") (pinfunction "2_2") (pintype "passive"))
      (node (ref "C82") (pin "2") (pinfunction "2_2") (pintype "passive"))
      (node (ref "IC1") (pin "8") (pinfunction "VCC_8") (pintype "power_in"))
      (node (ref "J1") (pin "1") (pinfunction "1_1") (pintype "passive"))
      (node (ref "POWER-IN") (pin "1") (pinfunction "1_1") (pintype "passive"))
      (node (ref "R1") (pin "1") (pinfunction "1_1") (pintype "passive"))
    )
    (net (code "68") (name "unconnected-(APA104-60-DOUT-Pad2)") (class "Default")
      (node (ref "APA104-60") (pin "2") (pinfunction "DOUT_2") (pintype "output"))
    )
  )
)
